# MODULE_SCH.net
KiCad netlist of a schematic drawn in Altium Designer
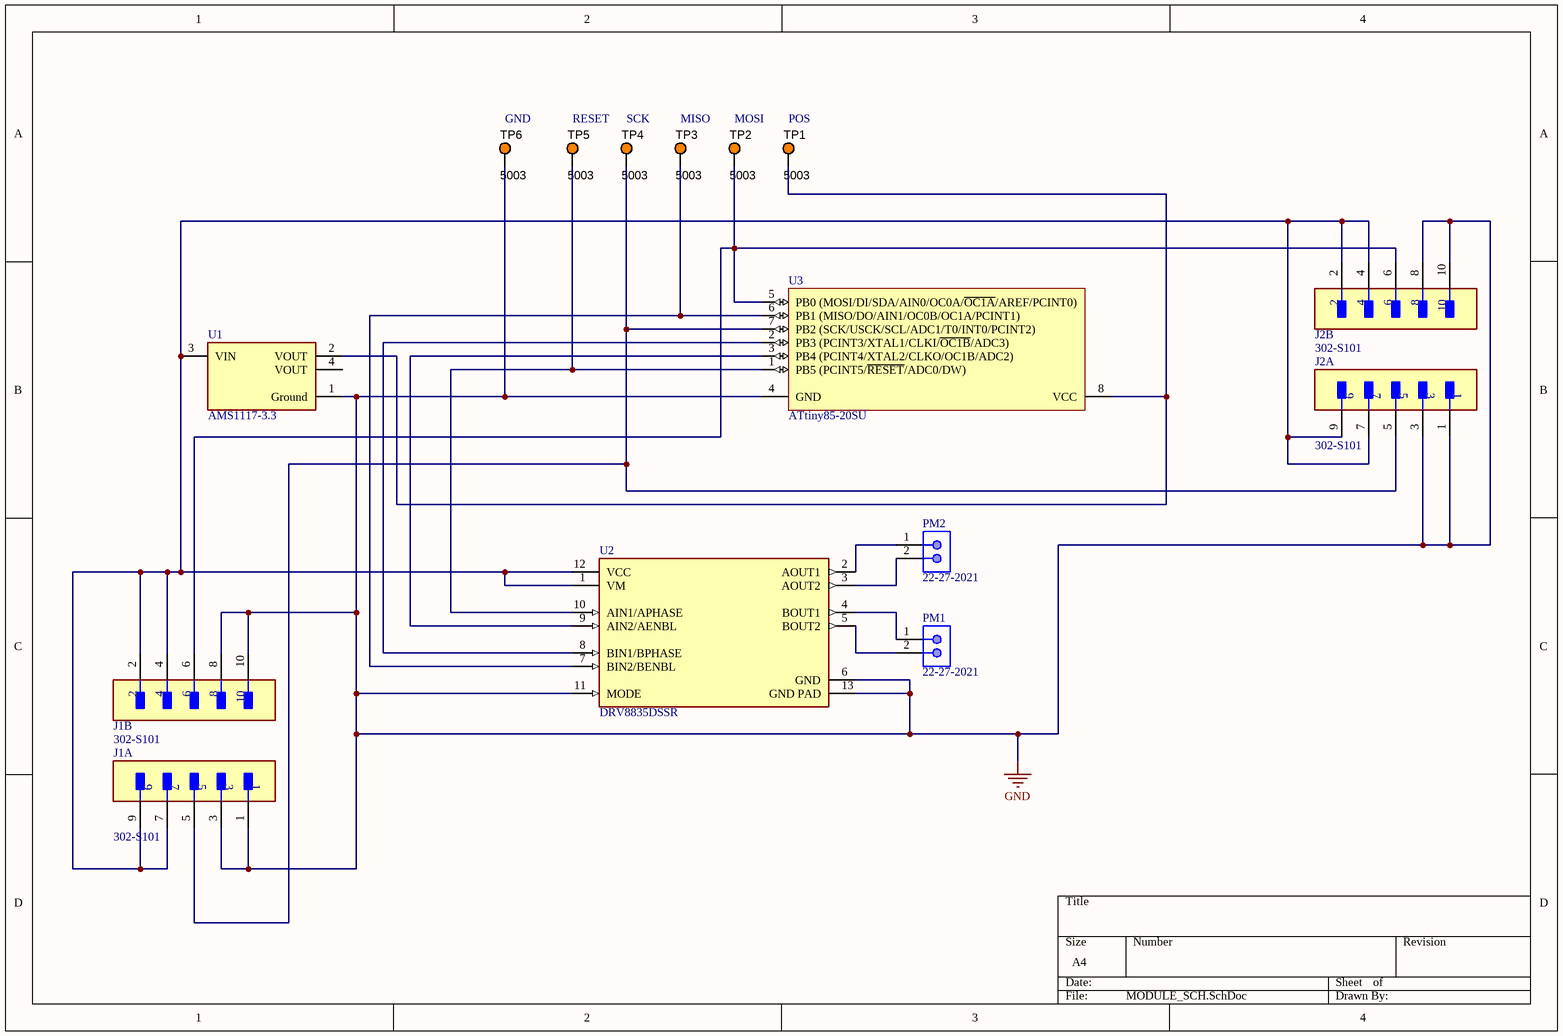
[diagram p0: MODULE_SCH.SchDoc]

(export (version "E")
  (design (tool "Eeschema 10.0.6"))
  (components
    (comp (ref "J1")
      (value "302-S101")
      (footprint "FP-302-S101-MFG")
      (description "CONN HEADER VERT 10POS 2.54MM")
      (libsource (lib "") (part "544f42128f4185dcb88ce1ce9bf1982_1"))
    )
    (comp (ref "J2")
      (value "302-S101")
      (footprint "FP-302-S101-MFG")
      (description "CONN HEADER VERT 10POS 2.54MM")
      (libsource (lib "Altium Content Vault") (part "544f42128f4185dcb88ce1ce9bf1982"))
    )
    (comp (ref "PM1")
      (value "22-27-2021")
      (footprint "MOLX-22-27-2021_V")
      (fields (field (name "MANUFACTURER") "Molex") (field (name "PARTNUMBER") "0022272021"))
      (libsource (lib "Altium Content Vault") (part "CN-1P-M-R2"))
    )
    (comp (ref "PM2")
      (value "22-27-2021")
      (footprint "MOLX-22-27-2021_V")
      (fields (field (name "MANUFACTURER") "Molex") (field (name "PARTNUMBER") "0022272021"))
      (libsource (lib "Altium Content Vault") (part "CN-1P-M-R2"))
    )
    (comp (ref "TP1")
      (value "5003")
      (footprint "KSTN-5003")
      (description "Test Point, Orange, 1-Pin THD, RoHS")
      (libsource (lib "Altium Content Vault") (part "TESTPOINT_ORANGE"))
    )
    (comp (ref "TP2")
      (value "5003")
      (footprint "KSTN-5003")
      (description "Test Point, Orange, 1-Pin THD, RoHS")
      (libsource (lib "Altium Content Vault") (part "TESTPOINT_ORANGE"))
    )
    (comp (ref "TP3")
      (value "5003")
      (footprint "KSTN-5003")
      (description "Test Point, Orange, 1-Pin THD, RoHS")
      (libsource (lib "Altium Content Vault") (part "TESTPOINT_ORANGE"))
    )
    (comp (ref "TP4")
      (value "5003")
      (footprint "KSTN-5003")
      (description "Test Point, Orange, 1-Pin THD, RoHS")
      (libsource (lib "Altium Content Vault") (part "TESTPOINT_ORANGE"))
    )
    (comp (ref "TP5")
      (value "5003")
      (footprint "KSTN-5003")
      (description "Test Point, Orange, 1-Pin THD, RoHS")
      (libsource (lib "Altium Content Vault") (part "TESTPOINT_ORANGE"))
    )
    (comp (ref "TP6")
      (value "5003")
      (footprint "KSTN-5003")
      (description "Test Point, Orange, 1-Pin THD, RoHS")
      (libsource (lib "Altium Content Vault") (part "TESTPOINT_ORANGE"))
    )
    (comp (ref "U1")
      (value "AMS1117-3.3")
      (footprint "FP-AMS1117-IPC_C")
      (description "LDO Voltage Regulators 1A, 3.3V")
      (fields
        (field (name "OCTOPART") "https://octopart.com/ams1117-3.3-advanced+monolithic+systems-25899300")
        (field (name "MANUFACTURER") "Advanced Monolithic Systems")
      )
      (libsource (lib "Altium Content Vault") (part "8bdbb5f8e77002000e30dd2845d0354"))
    )
    (comp (ref "U2")
      (value "DRV8835DSSR")
      (footprint "FP-DSS0012A-MFG")
      (description "IC MTR DRVR BIPOLAR 2-7V 12WSON")
      (libsource (lib "Altium Content Vault") (part "82e44215b819ffefb0872ba7d978039"))
    )
    (comp (ref "U3")
      (value "ATtiny85-20SU")
      (footprint "8S2_M")
      (libsource (lib "Altium Content Vault") (part "MC-8B-ATT25-IL8"))
    )
  )
  (nets
    (net (code "1") (name "GND") (class "Default")
      (node (ref "J1") (pin "1") (pinfunction "1_1") (pintype "passive"))
      (node (ref "J1") (pin "10") (pinfunction "10_10") (pintype "passive"))
      (node (ref "J1") (pin "3") (pinfunction "3_3") (pintype "passive"))
      (node (ref "J1") (pin "8") (pinfunction "8_8") (pintype "passive"))
      (node (ref "J2") (pin "1") (pinfunction "1_1") (pintype "passive"))
      (node (ref "J2") (pin "10") (pinfunction "10_10") (pintype "passive"))
      (node (ref "J2") (pin "3") (pinfunction "3_3") (pintype "passive"))
      (node (ref "J2") (pin "8") (pinfunction "8_8") (pintype "passive"))
      (node (ref "TP6") (pin "1") (pinfunction "1_1") (pintype "passive"))
      (node (ref "U1") (pin "1") (pinfunction "Ground_1") (pintype "power_in"))
      (node (ref "U2") (pin "11") (pinfunction "MODE_11") (pintype "input"))
      (node (ref "U2") (pin "13") (pinfunction "GND_PAD_13") (pintype "power_in"))
      (node (ref "U2") (pin "6") (pinfunction "GND_6") (pintype "power_in"))
      (node (ref "U3") (pin "4") (pinfunction "GND_4") (pintype "power_in"))
    )
    (net (code "2") (name "Net-(U1-VIN)") (class "Default")
      (node (ref "J1") (pin "2") (pinfunction "2_2") (pintype "passive"))
      (node (ref "J1") (pin "4") (pinfunction "4_4") (pintype "passive"))
      (node (ref "J1") (pin "7") (pinfunction "7_7") (pintype "passive"))
      (node (ref "J1") (pin "9") (pinfunction "9_9") (pintype "passive"))
      (node (ref "J2") (pin "2") (pinfunction "2_2") (pintype "passive"))
      (node (ref "J2") (pin "4") (pinfunction "4_4") (pintype "passive"))
      (node (ref "J2") (pin "7") (pinfunction "7_7") (pintype "passive"))
      (node (ref "J2") (pin "9") (pinfunction "9_9") (pintype "passive"))
      (node (ref "U1") (pin "3") (pinfunction "VIN_3") (pintype "power_in"))
      (node (ref "U2") (pin "1") (pinfunction "VM_1") (pintype "power_in"))
      (node (ref "U2") (pin "12") (pinfunction "VCC_12") (pintype "power_in"))
    )
    (net (code "3") (name "Net-(U2-AIN1{slash}APHASE)") (class "Default")
      (node (ref "TP5") (pin "1") (pinfunction "1_1") (pintype "passive"))
      (node (ref "U2") (pin "10") (pinfunction "AIN1/APHASE_10") (pintype "input"))
      (node (ref "U3") (pin "1") (pinfunction "PB5_(PCINT5/~{RESET}/ADC0/DW)_1") (pintype "bidirectional"))
    )
    (net (code "4") (name "Net-(U2-AIN2{slash}AENBL)") (class "Default")
      (node (ref "U2") (pin "9") (pinfunction "AIN2/AENBL_9") (pintype "input"))
      (node (ref "U3") (pin "3") (pinfunction "PB4_(PCINT4/XTAL2/CLKO/OC1B/ADC2)_3") (pintype "bidirectional"))
    )
    (net (code "5") (name "Net-(U2-AOUT1)") (class "Default")
      (node (ref "PM2") (pin "1") (pinfunction "1_1") (pintype "passive"))
      (node (ref "U2") (pin "2") (pinfunction "AOUT1_2") (pintype "output"))
    )
    (net (code "6") (name "Net-(U2-AOUT2)") (class "Default")
      (node (ref "PM2") (pin "2") (pinfunction "2_2") (pintype "passive"))
      (node (ref "U2") (pin "3") (pinfunction "AOUT2_3") (pintype "output"))
    )
    (net (code "7") (name "Net-(U2-BIN1{slash}BPHASE)") (class "Default")
      (node (ref "U2") (pin "8") (pinfunction "BIN1/BPHASE_8") (pintype "input"))
      (node (ref "U3") (pin "2") (pinfunction "PB3_(PCINT3/XTAL1/CLKI/~{OC1B}/ADC3)_2") (pintype "bidirectional"))
    )
    (net (code "8") (name "Net-(U2-BIN2{slash}BENBL)") (class "Default")
      (node (ref "TP3") (pin "1") (pinfunction "1_1") (pintype "passive"))
      (node (ref "U2") (pin "7") (pinfunction "BIN2/BENBL_7") (pintype "input"))
      (node (ref "U3") (pin "6") (pinfunction "PB1_(MISO/DO/AIN1/OC0B/OC1A/PCINT1)_6") (pintype "bidirectional"))
    )
    (net (code "9") (name "Net-(U2-BOUT1)") (class "Default")
      (node (ref "PM1") (pin "1") (pinfunction "1_1") (pintype "passive"))
      (node (ref "U2") (pin "4") (pinfunction "BOUT1_4") (pintype "output"))
    )
    (net (code "10") (name "Net-(U2-BOUT2)") (class "Default")
      (node (ref "PM1") (pin "2") (pinfunction "2_2") (pintype "passive"))
      (node (ref "U2") (pin "5") (pinfunction "BOUT2_5") (pintype "output"))
    )
    (net (code "11") (name "Net-(U3-PB0_(MOSI{slash}DI{slash}SDA{slash}AIN0{slash}OC0A{slash}~{OC1A}{slash}AREF{slash}PCINT0))") (class "Default")
      (node (ref "J1") (pin "6") (pinfunction "6_6") (pintype "passive"))
      (node (ref "J2") (pin "6") (pinfunction "6_6") (pintype "passive"))
      (node (ref "TP2") (pin "1") (pinfunction "1_1") (pintype "passive"))
      (node (ref "U3") (pin "5") (pinfunction "PB0_(MOSI/DI/SDA/AIN0/OC0A/~{OC1A}/AREF/PCINT0)_5") (pintype "bidirectional"))
    )
    (net (code "12") (name "Net-(U3-PB2_(SCK{slash}USCK{slash}SCL{slash}ADC1{slash}T0{slash}INT0{slash}PCINT2))") (class "Default")
      (node (ref "J1") (pin "5") (pinfunction "5_5") (pintype "passive"))
      (node (ref "J2") (pin "5") (pinfunction "5_5") (pintype "passive"))
      (node (ref "TP4") (pin "1") (pinfunction "1_1") (pintype "passive"))
      (node (ref "U3") (pin "7") (pinfunction "PB2_(SCK/USCK/SCL/ADC1/T0/INT0/PCINT2)_7") (pintype "bidirectional"))
    )
    (net (code "13") (name "Net-(U3-VCC)") (class "Default")
      (node (ref "TP1") (pin "1") (pinfunction "1_1") (pintype "passive"))
      (node (ref "U1") (pin "2") (pinfunction "VOUT_2") (pintype "passive"))
      (node (ref "U3") (pin "8") (pinfunction "VCC_8") (pintype "power_in"))
    )
    (net (code "14") (name "unconnected-(U1-VOUT-Pad4)") (class "Default")
      (node (ref "U1") (pin "4") (pinfunction "VOUT_4") (pintype "passive"))
    )
  )
)
